# misc_connectors.net
KiCad netlist of a schematic drawn in Altium Designer
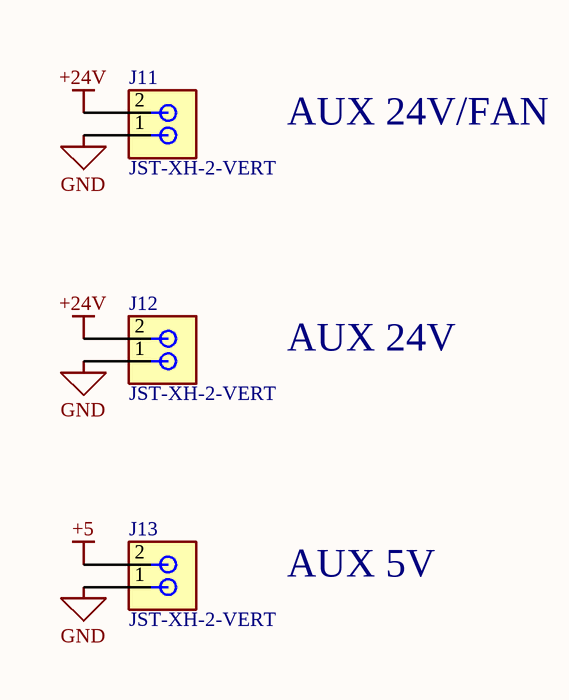
[diagram p0: misc_connectors.SchDoc]

(export (version "E")
  (design (tool "Eeschema 10.0.6"))
  (components
    (comp (ref "J11")
      (value "JST-XH-2-VERT")
      (footprint "JST-XH-2p-vert")
      (description "Konektor: kabel-pl.spoj; zásuvka; vidlice; PIN: 2; XH; 3A; 250V; THT")
      (fields (field (name "TME PART") "B2B-XH-A"))
      (libsource (lib "Kubikova ultra knihovna") (part "JST-XH-2-VERT"))
    )
    (comp (ref "J12")
      (value "JST-XH-2-VERT")
      (footprint "JST-XH-2p-vert")
      (description "Konektor: kabel-pl.spoj; zásuvka; vidlice; PIN: 2; XH; 3A; 250V; THT")
      (fields (field (name "TME PART") "B2B-XH-A"))
      (libsource (lib "Kubikova ultra knihovna") (part "JST-XH-2-VERT"))
    )
    (comp (ref "J13")
      (value "JST-XH-2-VERT")
      (footprint "JST-XH-2p-vert")
      (description "Konektor: kabel-pl.spoj; zásuvka; vidlice; PIN: 2; XH; 3A; 250V; THT")
      (fields (field (name "TME PART") "B2B-XH-A"))
      (libsource (lib "Kubikova ultra knihovna") (part "JST-XH-2-VERT"))
    )
  )
  (nets
    (net (code "1") (name "+5") (class "Default")
      (node (ref "J13") (pin "2") (pinfunction "2_2") (pintype "passive"))
    )
    (net (code "2") (name "+24V") (class "Default")
      (node (ref "J11") (pin "2") (pinfunction "2_2") (pintype "passive"))
      (node (ref "J12") (pin "2") (pinfunction "2_2") (pintype "passive"))
    )
    (net (code "3") (name "GND") (class "Default")
      (node (ref "J11") (pin "1") (pinfunction "1_1") (pintype "passive"))
      (node (ref "J12") (pin "1") (pinfunction "1_1") (pintype "passive"))
      (node (ref "J13") (pin "1") (pinfunction "1_1") (pintype "passive"))
    )
  )
)
